# Sheet2.net
KiCad netlist of a schematic drawn in Altium Designer
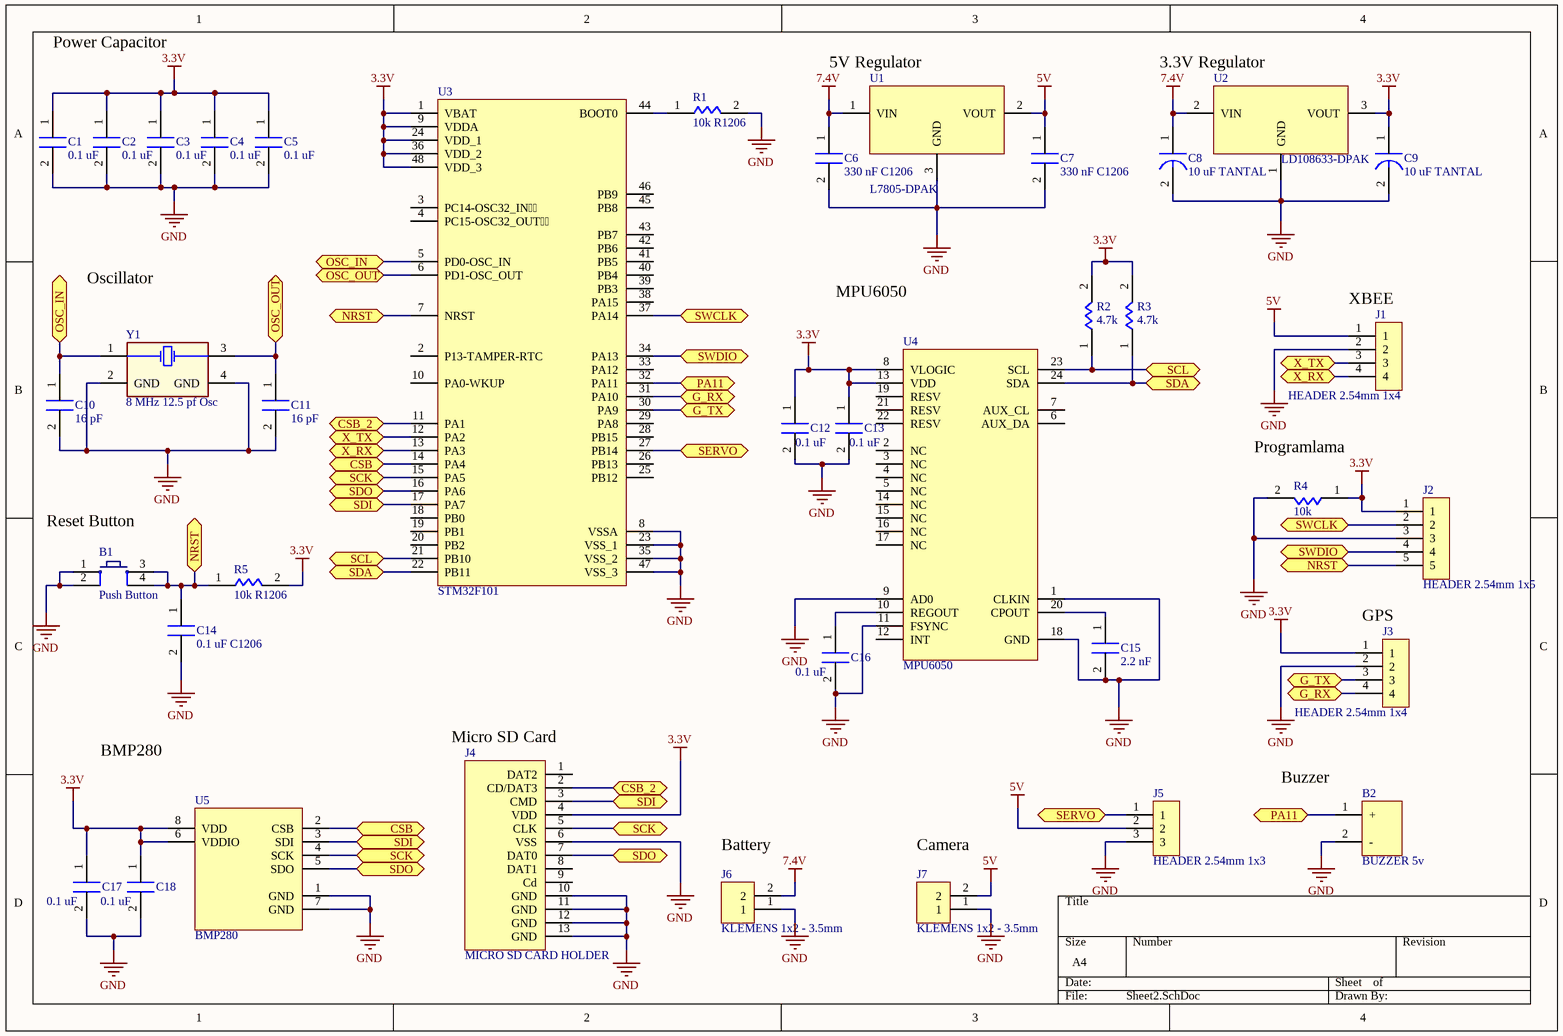
[diagram p0: Sheet2.SchDoc]

(export (version "E")
  (design (tool "Eeschema 10.0.6"))
  (components
    (comp (ref "B1")
      (value "Push Button")
      (footprint "PUSB BUTTON-SMD")
      (description "Smd Push Button")
      (libsource (lib "STM32") (part "Push Button"))
    )
    (comp (ref "B2") (value "BUZZER 5v") (footprint "BUZZER 5v") (libsource (lib "STM32") (part "BUZZER 5v")))
    (comp (ref "C1")
      (value "0.1 uF")
      (footprint "C1206")
      (description "0.1 uF C1206")
      (libsource (lib "STM32") (part "0.1 uF C1206"))
    )
    (comp (ref "C2")
      (value "0.1 uF")
      (footprint "C1206")
      (description "0.1 uF C1206")
      (libsource (lib "STM32") (part "0.1 uF C1206"))
    )
    (comp (ref "C3")
      (value "0.1 uF")
      (footprint "C1206")
      (description "0.1 uF C1206")
      (libsource (lib "STM32") (part "0.1 uF C1206"))
    )
    (comp (ref "C4")
      (value "0.1 uF")
      (footprint "C1206")
      (description "0.1 uF C1206")
      (libsource (lib "STM32") (part "0.1 uF C1206"))
    )
    (comp (ref "C5")
      (value "0.1 uF")
      (footprint "C1206")
      (description "0.1 uF C1206")
      (libsource (lib "STM32") (part "0.1 uF C1206"))
    )
    (comp (ref "C6")
      (value "330 nF C1206")
      (footprint "C1206")
      (libsource (lib "STM32") (part "330 nF C1206"))
    )
    (comp (ref "C7")
      (value "330 nF C1206")
      (footprint "C1206")
      (libsource (lib "STM32") (part "330 nF C1206"))
    )
    (comp (ref "C8")
      (value "10 uF TANTAL")
      (footprint "C1206 - TANTAL")
      (description "10 uF C1206 - TANTAL")
      (libsource (lib "STM32") (part "10 uF TANTAL"))
    )
    (comp (ref "C9")
      (value "10 uF TANTAL")
      (footprint "C1206 - TANTAL")
      (description "10 uF C1206 - TANTAL")
      (libsource (lib "STM32") (part "10 uF TANTAL"))
    )
    (comp (ref "C10") (value "16 pF") (footprint "C1206") (libsource (lib "STM32") (part "16 pF")))
    (comp (ref "C11") (value "16 pF") (footprint "C1206") (libsource (lib "STM32") (part "16 pF")))
    (comp (ref "C12")
      (value "0.1 uF")
      (footprint "C1206")
      (description "0.1 uF C1206")
      (libsource (lib "STM32") (part "0.1 uF C1206"))
    )
    (comp (ref "C13")
      (value "0.1 uF")
      (footprint "C1206")
      (description "0.1 uF C1206")
      (libsource (lib "STM32") (part "0.1 uF C1206"))
    )
    (comp (ref "C14")
      (value "0.1 uF C1206")
      (footprint "C1206")
      (libsource (lib "STM32") (part "0.1 uF C1206"))
    )
    (comp (ref "C15")
      (value "2.2 nF")
      (footprint "C1206")
      (description "2.2 nF C1206")
      (libsource (lib "STM32") (part "2.2 nF"))
    )
    (comp (ref "C16")
      (value "0.1 uF")
      (footprint "C1206")
      (description "0.1 uF C1206")
      (libsource (lib "STM32") (part "0.1 uF C1206"))
    )
    (comp (ref "C17")
      (value "0.1 uF")
      (footprint "C1206")
      (description "0.1 uF C1206")
      (libsource (lib "STM32") (part "0.1 uF C1206"))
    )
    (comp (ref "C18")
      (value "0.1 uF")
      (footprint "C1206")
      (description "0.1 uF C1206")
      (libsource (lib "STM32") (part "0.1 uF C1206"))
    )
    (comp (ref "J1")
      (value "HEADER 2.54mm 1x4")
      (footprint "HEADER 2.54mm 1x4")
      (libsource (lib "STM32") (part "HEADER 2.54mm 1x4"))
    )
    (comp (ref "J2")
      (value "HEADER 2.54mm 1x5")
      (footprint "HEADER 2.54mm 1x5")
      (libsource (lib "STM32") (part "HEADER 2.54mm 1x5"))
    )
    (comp (ref "J3")
      (value "HEADER 2.54mm 1x4")
      (footprint "HEADER 2.54mm 1x4")
      (libsource (lib "STM32") (part "HEADER 2.54mm 1x4"))
    )
    (comp (ref "J4")
      (value "MICRO SD CARD HOLDER")
      (footprint "MICRO SD CARD HOLDER")
      (description "MICRO SD CARD HOLDER KLS1-TF-003 Micro SD Card Connector")
      (libsource (lib "STM32") (part "MICRO SD CARD HOLDER"))
    )
    (comp (ref "J5")
      (value "HEADER 2.54mm 1x3")
      (footprint "HEADER 2.54mm 1x3")
      (libsource (lib "STM32") (part "HEADER 2.54mm 1x3"))
    )
    (comp (ref "J6")
      (value "KLEMENS 1x2 - 3.5mm")
      (footprint "KLEMENS 1x2 - 3.5mm")
      (libsource (lib "STM32") (part "KLEMENS 1x2 - 3.5mm"))
    )
    (comp (ref "J7")
      (value "KLEMENS 1x2 - 3.5mm")
      (footprint "KLEMENS 1x2 - 3.5mm")
      (libsource (lib "STM32") (part "KLEMENS 1x2 - 3.5mm"))
    )
    (comp (ref "R1")
      (value "10k R1206")
      (footprint "R1206 RESISTOR")
      (libsource (lib "STM32") (part "10k R1206"))
    )
    (comp (ref "R2")
      (value "4.7k")
      (footprint "R1206 RESISTOR")
      (description "4.7k R1206")
      (libsource (lib "STM32") (part "4.7k"))
    )
    (comp (ref "R3")
      (value "4.7k")
      (footprint "R1206 RESISTOR")
      (description "4.7k R1206")
      (libsource (lib "STM32") (part "4.7k"))
    )
    (comp (ref "R4")
      (value "10k")
      (footprint "R1206 RESISTOR")
      (description "10k R1206")
      (libsource (lib "STM32") (part "10k"))
    )
    (comp (ref "R5")
      (value "10k R1206")
      (footprint "R1206 RESISTOR")
      (libsource (lib "STM32") (part "10k R1206"))
    )
    (comp (ref "U1")
      (value "L7805-DPAK")
      (footprint "DPAK228P972X240-3N")
      (description "L7805 5V REGULATOR SMD PACKET")
      (libsource (lib "STM32") (part "L7805-DPAK"))
    )
    (comp (ref "U2")
      (value "LD108633-DPAK")
      (footprint "DPAK228P972X240-3N")
      (description "LD108633 3.3V REGULATOR DPAK")
      (libsource (lib "STM32") (part "LD108633-DPAK"))
    )
    (comp (ref "U3")
      (value "STM32F101")
      (footprint "LQPF48_STM")
      (description "STM32F101 48PIN MICROPROCESSOR")
      (libsource (lib "STM32") (part "STM32F101"))
    )
    (comp (ref "U4")
      (value "MPU6050")
      (footprint "QFN50P400X400X95_HS-25N")
      (description "MPU GYRO")
      (libsource (lib "STM32") (part "MPU6050"))
    )
    (comp (ref "U5")
      (value "BMP280")
      (footprint "BMP280")
      (description "BMP280 PRESSURE")
      (libsource (lib "STM32") (part "BMP280"))
    )
    (comp (ref "Y1")
      (value "8 MHz 12.5 pf Osc")
      (footprint "8 MHZ Osc.")
      (libsource (lib "STM32") (part "8 MHz 12.5 pf Osc"))
    )
  )
  (nets
    (net (code "1") (name "/CSB") (class "Default")
      (node (ref "U3") (pin "14") (pinfunction "PA4_14") (pintype "passive"))
      (node (ref "U5") (pin "2") (pinfunction "CSB_2") (pintype "passive"))
    )
    (net (code "2") (name "/CSB_2") (class "Default")
      (node (ref "J4") (pin "2") (pinfunction "CD/DAT3_2") (pintype "passive"))
      (node (ref "U3") (pin "11") (pinfunction "PA1_11") (pintype "passive"))
    )
    (net (code "3") (name "/G_RX") (class "Default")
      (node (ref "J3") (pin "4") (pinfunction "4_4") (pintype "passive"))
      (node (ref "U3") (pin "31") (pinfunction "PA10_31") (pintype "passive"))
    )
    (net (code "4") (name "/G_TX") (class "Default")
      (node (ref "J3") (pin "3") (pinfunction "3_3") (pintype "passive"))
      (node (ref "U3") (pin "30") (pinfunction "PA9_30") (pintype "passive"))
    )
    (net (code "5") (name "/NRST") (class "Default")
      (node (ref "B1") (pin "3") (pinfunction "3_3") (pintype "passive"))
      (node (ref "B1") (pin "4") (pinfunction "4_4") (pintype "passive"))
      (node (ref "C14") (pin "1") (pinfunction "1_1") (pintype "passive"))
      (node (ref "J2") (pin "5") (pinfunction "5_5") (pintype "passive"))
      (node (ref "R5") (pin "1") (pinfunction "1_1") (pintype "passive"))
      (node (ref "U3") (pin "7") (pinfunction "NRST_7") (pintype "passive"))
    )
    (net (code "6") (name "/OSC_IN") (class "Default")
      (node (ref "C10") (pin "1") (pinfunction "1_1") (pintype "passive"))
      (node (ref "U3") (pin "5") (pinfunction "PD0-OSC_IN_5") (pintype "passive"))
      (node (ref "Y1") (pin "1") (pintype "passive"))
    )
    (net (code "7") (name "/OSC_OUT") (class "Default")
      (node (ref "C11") (pin "1") (pinfunction "1_1") (pintype "passive"))
      (node (ref "U3") (pin "6") (pinfunction "PD1-OSC_OUT_6") (pintype "passive"))
      (node (ref "Y1") (pin "3") (pintype "passive"))
    )
    (net (code "8") (name "/PA11") (class "Default")
      (node (ref "B2") (pin "1") (pinfunction "+_1") (pintype "passive"))
      (node (ref "U3") (pin "32") (pinfunction "PA11_32") (pintype "passive"))
    )
    (net (code "9") (name "/SCK") (class "Default")
      (node (ref "J4") (pin "5") (pinfunction "CLK_5") (pintype "passive"))
      (node (ref "U3") (pin "15") (pinfunction "PA5_15") (pintype "passive"))
      (node (ref "U5") (pin "4") (pinfunction "SCK_4") (pintype "passive"))
    )
    (net (code "10") (name "/SCL") (class "Default")
      (node (ref "R2") (pin "1") (pinfunction "1_1") (pintype "passive"))
      (node (ref "U3") (pin "21") (pinfunction "PB10_21") (pintype "passive"))
      (node (ref "U4") (pin "23") (pinfunction "SCL_23") (pintype "passive"))
    )
    (net (code "11") (name "/SDA") (class "Default")
      (node (ref "R3") (pin "1") (pinfunction "1_1") (pintype "passive"))
      (node (ref "U3") (pin "22") (pinfunction "PB11_22") (pintype "passive"))
      (node (ref "U4") (pin "24") (pinfunction "SDA_24") (pintype "passive"))
    )
    (net (code "12") (name "/SDI") (class "Default")
      (node (ref "J4") (pin "3") (pinfunction "CMD_3") (pintype "passive"))
      (node (ref "U3") (pin "17") (pinfunction "PA7_17") (pintype "passive"))
      (node (ref "U5") (pin "3") (pinfunction "SDI_3") (pintype "passive"))
    )
    (net (code "13") (name "/SDO") (class "Default")
      (node (ref "J4") (pin "7") (pinfunction "DAT0_7") (pintype "passive"))
      (node (ref "U3") (pin "16") (pinfunction "PA6_16") (pintype "passive"))
      (node (ref "U5") (pin "5") (pinfunction "SDO_5") (pintype "passive"))
    )
    (net (code "14") (name "/SERVO") (class "Default")
      (node (ref "J5") (pin "1") (pinfunction "1_1") (pintype "passive"))
      (node (ref "U3") (pin "27") (pinfunction "PB14_27") (pintype "passive"))
    )
    (net (code "15") (name "/SWCLK") (class "Default")
      (node (ref "J2") (pin "2") (pinfunction "2_2") (pintype "passive"))
      (node (ref "U3") (pin "37") (pinfunction "PA14_37") (pintype "passive"))
    )
    (net (code "16") (name "/SWDIO") (class "Default")
      (node (ref "J2") (pin "4") (pinfunction "4_4") (pintype "passive"))
      (node (ref "U3") (pin "34") (pinfunction "PA13_34") (pintype "passive"))
    )
    (net (code "17") (name "/X_RX") (class "Default")
      (node (ref "J1") (pin "4") (pinfunction "4_4") (pintype "passive"))
      (node (ref "U3") (pin "13") (pinfunction "PA3_13") (pintype "passive"))
    )
    (net (code "18") (name "/X_TX") (class "Default")
      (node (ref "J1") (pin "3") (pinfunction "3_3") (pintype "passive"))
      (node (ref "U3") (pin "12") (pinfunction "PA2_12") (pintype "passive"))
    )
    (net (code "19") (name "3.3V") (class "Default")
      (node (ref "C1") (pin "1") (pinfunction "1_1") (pintype "passive"))
      (node (ref "C12") (pin "1") (pinfunction "1_1") (pintype "passive"))
      (node (ref "C13") (pin "1") (pinfunction "1_1") (pintype "passive"))
      (node (ref "C17") (pin "1") (pinfunction "1_1") (pintype "passive"))
      (node (ref "C18") (pin "1") (pinfunction "1_1") (pintype "passive"))
      (node (ref "C2") (pin "1") (pinfunction "1_1") (pintype "passive"))
      (node (ref "C3") (pin "1") (pinfunction "1_1") (pintype "passive"))
      (node (ref "C4") (pin "1") (pinfunction "1_1") (pintype "passive"))
      (node (ref "C5") (pin "1") (pinfunction "1_1") (pintype "passive"))
      (node (ref "C9") (pin "1") (pinfunction "1_1") (pintype "passive"))
      (node (ref "J2") (pin "1") (pinfunction "1_1") (pintype "passive"))
      (node (ref "J3") (pin "1") (pinfunction "1_1") (pintype "passive"))
      (node (ref "J4") (pin "4") (pinfunction "VDD_4") (pintype "passive"))
      (node (ref "R2") (pin "2") (pinfunction "2_2") (pintype "passive"))
      (node (ref "R3") (pin "2") (pinfunction "2_2") (pintype "passive"))
      (node (ref "R4") (pin "1") (pinfunction "1_1") (pintype "passive"))
      (node (ref "R5") (pin "2") (pinfunction "2_2") (pintype "passive"))
      (node (ref "U2") (pin "3") (pinfunction "VOUT_3") (pintype "passive"))
      (node (ref "U3") (pin "1") (pinfunction "VBAT_1") (pintype "passive"))
      (node (ref "U3") (pin "24") (pinfunction "VDD_1_24") (pintype "passive"))
      (node (ref "U3") (pin "36") (pinfunction "VDD_2_36") (pintype "passive"))
      (node (ref "U3") (pin "48") (pinfunction "VDD_3_48") (pintype "passive"))
      (node (ref "U3") (pin "9") (pinfunction "VDDA_9") (pintype "passive"))
      (node (ref "U4") (pin "13") (pinfunction "VDD_13") (pintype "passive"))
      (node (ref "U4") (pin "8") (pinfunction "VLOGIC_8") (pintype "passive"))
      (node (ref "U5") (pin "6") (pinfunction "VDDIO_6") (pintype "passive"))
      (node (ref "U5") (pin "8") (pinfunction "VDD_8") (pintype "passive"))
    )
    (net (code "20") (name "5V") (class "Default")
      (node (ref "C7") (pin "1") (pinfunction "1_1") (pintype "passive"))
      (node (ref "J1") (pin "1") (pinfunction "1_1") (pintype "passive"))
      (node (ref "J5") (pin "2") (pinfunction "2_2") (pintype "passive"))
      (node (ref "J7") (pin "2") (pinfunction "2_2") (pintype "passive"))
      (node (ref "U1") (pin "2") (pinfunction "VOUT_2") (pintype "passive"))
    )
    (net (code "21") (name "7.4V") (class "Default")
      (node (ref "C6") (pin "1") (pinfunction "1_1") (pintype "passive"))
      (node (ref "C8") (pin "1") (pinfunction "1_1") (pintype "passive"))
      (node (ref "J6") (pin "2") (pinfunction "2_2") (pintype "passive"))
      (node (ref "U1") (pin "1") (pinfunction "VIN_1") (pintype "passive"))
      (node (ref "U2") (pin "2") (pinfunction "VIN_2") (pintype "passive"))
    )
    (net (code "22") (name "GND") (class "Default")
      (node (ref "B1") (pin "1") (pinfunction "1_1") (pintype "passive"))
      (node (ref "B1") (pin "2") (pinfunction "2_2") (pintype "passive"))
      (node (ref "B2") (pin "2") (pinfunction "-_2") (pintype "passive"))
      (node (ref "C1") (pin "2") (pinfunction "2_2") (pintype "passive"))
      (node (ref "C10") (pin "2") (pinfunction "2_2") (pintype "passive"))
      (node (ref "C11") (pin "2") (pinfunction "2_2") (pintype "passive"))
      (node (ref "C12") (pin "2") (pinfunction "2_2") (pintype "passive"))
      (node (ref "C13") (pin "2") (pinfunction "2_2") (pintype "passive"))
      (node (ref "C14") (pin "2") (pinfunction "2_2") (pintype "passive"))
      (node (ref "C15") (pin "2") (pinfunction "2_2") (pintype "passive"))
      (node (ref "C16") (pin "2") (pinfunction "2_2") (pintype "passive"))
      (node (ref "C17") (pin "2") (pinfunction "2_2") (pintype "passive"))
      (node (ref "C18") (pin "2") (pinfunction "2_2") (pintype "passive"))
      (node (ref "C2") (pin "2") (pinfunction "2_2") (pintype "passive"))
      (node (ref "C3") (pin "2") (pinfunction "2_2") (pintype "passive"))
      (node (ref "C4") (pin "2") (pinfunction "2_2") (pintype "passive"))
      (node (ref "C5") (pin "2") (pinfunction "2_2") (pintype "passive"))
      (node (ref "C6") (pin "2") (pinfunction "2_2") (pintype "passive"))
      (node (ref "C7") (pin "2") (pinfunction "2_2") (pintype "passive"))
      (node (ref "C8") (pin "2") (pinfunction "2_2") (pintype "passive"))
      (node (ref "C9") (pin "2") (pinfunction "2_2") (pintype "passive"))
      (node (ref "J1") (pin "2") (pinfunction "2_2") (pintype "passive"))
      (node (ref "J2") (pin "3") (pinfunction "3_3") (pintype "passive"))
      (node (ref "J3") (pin "2") (pinfunction "2_2") (pintype "passive"))
      (node (ref "J4") (pin "10") (pinfunction "GND_10") (pintype "passive"))
      (node (ref "J4") (pin "11") (pinfunction "GND_11") (pintype "passive"))
      (node (ref "J4") (pin "12") (pinfunction "GND_12") (pintype "passive"))
      (node (ref "J4") (pin "13") (pinfunction "GND_13") (pintype "passive"))
      (node (ref "J4") (pin "6") (pinfunction "VSS_6") (pintype "passive"))
      (node (ref "J5") (pin "3") (pinfunction "3_3") (pintype "passive"))
      (node (ref "J6") (pin "1") (pinfunction "1_1") (pintype "passive"))
      (node (ref "J7") (pin "1") (pinfunction "1_1") (pintype "passive"))
      (node (ref "R1") (pin "2") (pinfunction "2_2") (pintype "passive"))
      (node (ref "R4") (pin "2") (pinfunction "2_2") (pintype "passive"))
      (node (ref "U1") (pin "3") (pinfunction "GND_3") (pintype "passive"))
      (node (ref "U2") (pin "1") (pinfunction "GND_1") (pintype "passive"))
      (node (ref "U3") (pin "23") (pinfunction "VSS_1_23") (pintype "passive"))
      (node (ref "U3") (pin "35") (pinfunction "VSS_2_35") (pintype "passive"))
      (node (ref "U3") (pin "47") (pinfunction "VSS_3_47") (pintype "passive"))
      (node (ref "U3") (pin "8") (pinfunction "VSSA_8") (pintype "passive"))
      (node (ref "U4") (pin "1") (pinfunction "CLKIN_1") (pintype "passive"))
      (node (ref "U4") (pin "11") (pinfunction "FSYNC_11") (pintype "passive"))
      (node (ref "U4") (pin "18") (pinfunction "GND_18") (pintype "passive"))
      (node (ref "U4") (pin "9") (pinfunction "AD0_9") (pintype "passive"))
      (node (ref "U5") (pin "1") (pinfunction "GND_1") (pintype "passive"))
      (node (ref "U5") (pin "7") (pinfunction "GND_7") (pintype "passive"))
      (node (ref "Y1") (pin "2") (pinfunction "GND_2") (pintype "power_in"))
      (node (ref "Y1") (pin "4") (pinfunction "GND_4") (pintype "passive"))
    )
    (net (code "23") (name "Net-(U3-BOOT0)") (class "Default")
      (node (ref "R1") (pin "1") (pinfunction "1_1") (pintype "passive"))
      (node (ref "U3") (pin "44") (pinfunction "BOOT0_44") (pintype "passive"))
    )
    (net (code "24") (name "Net-(U4-CPOUT)") (class "Default")
      (node (ref "C15") (pin "1") (pinfunction "1_1") (pintype "passive"))
      (node (ref "U4") (pin "20") (pinfunction "CPOUT_20") (pintype "passive"))
    )
    (net (code "25") (name "Net-(U4-REGOUT)") (class "Default")
      (node (ref "C16") (pin "1") (pinfunction "1_1") (pintype "passive"))
      (node (ref "U4") (pin "10") (pinfunction "REGOUT_10") (pintype "passive"))
    )
    (net (code "26") (name "unconnected-(J4-Cd-Pad9)") (class "Default")
      (node (ref "J4") (pin "9") (pinfunction "Cd_9") (pintype "passive"))
    )
    (net (code "27") (name "unconnected-(J4-DAT1-Pad8)") (class "Default")
      (node (ref "J4") (pin "8") (pinfunction "DAT1_8") (pintype "passive"))
    )
    (net (code "28") (name "unconnected-(J4-DAT2-Pad1)") (class "Default")
      (node (ref "J4") (pin "1") (pinfunction "DAT2_1") (pintype "passive"))
    )
    (net (code "29") (name "unconnected-(U3-P13-TAMPER-RTC-Pad2)") (class "Default")
      (node (ref "U3") (pin "2") (pinfunction "P13-TAMPER-RTC_2") (pintype "passive"))
    )
    (net (code "30") (name "unconnected-(U3-PA0-WKUP-Pad10)") (class "Default")
      (node (ref "U3") (pin "10") (pinfunction "PA0-WKUP_10") (pintype "passive"))
    )
    (net (code "31") (name "unconnected-(U3-PA8-Pad29)") (class "Default")
      (node (ref "U3") (pin "29") (pinfunction "PA8_29") (pintype "passive"))
    )
    (net (code "32") (name "unconnected-(U3-PA12-Pad33)") (class "Default")
      (node (ref "U3") (pin "33") (pinfunction "PA12_33") (pintype "passive"))
    )
    (net (code "33") (name "unconnected-(U3-PA15-Pad38)") (class "Default")
      (node (ref "U3") (pin "38") (pinfunction "PA15_38") (pintype "passive"))
    )
    (net (code "34") (name "unconnected-(U3-PB0-Pad18)") (class "Default")
      (node (ref "U3") (pin "18") (pinfunction "PB0_18") (pintype "passive"))
    )
    (net (code "35") (name "unconnected-(U3-PB1-Pad19)") (class "Default")
      (node (ref "U3") (pin "19") (pinfunction "PB1_19") (pintype "passive"))
    )
    (net (code "36") (name "unconnected-(U3-PB2-Pad20)") (class "Default")
      (node (ref "U3") (pin "20") (pinfunction "PB2_20") (pintype "passive"))
    )
    (net (code "37") (name "unconnected-(U3-PB3-Pad39)") (class "Default")
      (node (ref "U3") (pin "39") (pinfunction "PB3_39") (pintype "passive"))
    )
    (net (code "38") (name "unconnected-(U3-PB4-Pad40)") (class "Default")
      (node (ref "U3") (pin "40") (pinfunction "PB4_40") (pintype "passive"))
    )
    (net (code "39") (name "unconnected-(U3-PB5-Pad41)") (class "Default")
      (node (ref "U3") (pin "41") (pinfunction "PB5_41") (pintype "passive"))
    )
    (net (code "40") (name "unconnected-(U3-PB6-Pad42)") (class "Default")
      (node (ref "U3") (pin "42") (pinfunction "PB6_42") (pintype "passive"))
    )
    (net (code "41") (name "unconnected-(U3-PB7-Pad43)") (class "Default")
      (node (ref "U3") (pin "43") (pinfunction "PB7_43") (pintype "passive"))
    )
    (net (code "42") (name "unconnected-(U3-PB8-Pad45)") (class "Default")
      (node (ref "U3") (pin "45") (pinfunction "PB8_45") (pintype "passive"))
    )
    (net (code "43") (name "unconnected-(U3-PB9-Pad46)") (class "Default")
      (node (ref "U3") (pin "46") (pinfunction "PB9_46") (pintype "passive"))
    )
    (net (code "44") (name "unconnected-(U3-PB12-Pad25)") (class "Default")
      (node (ref "U3") (pin "25") (pinfunction "PB12_25") (pintype "passive"))
    )
    (net (code "45") (name "unconnected-(U3-PB13-Pad26)") (class "Default")
      (node (ref "U3") (pin "26") (pinfunction "PB13_26") (pintype "passive"))
    )
    (net (code "46") (name "unconnected-(U3-PB15-Pad28)") (class "Default")
      (node (ref "U3") (pin "28") (pinfunction "PB15_28") (pintype "passive"))
    )
    (net (code "47") (name "unconnected-(U3-PC14-OSC32_IN-Pad3)") (class "Default")
      (node (ref "U3") (pin "3") (pinfunction "PC14-OSC32_IN_3") (pintype "passive"))
    )
    (net (code "48") (name "unconnected-(U3-PC15-OSC32_OUT-Pad4)") (class "Default")
      (node (ref "U3") (pin "4") (pinfunction "PC15-OSC32_OUT_4") (pintype "passive"))
    )
    (net (code "49") (name "unconnected-(U4-AUX_CL-Pad7)") (class "Default")
      (node (ref "U4") (pin "7") (pinfunction "AUX_CL_7") (pintype "passive"))
    )
    (net (code "50") (name "unconnected-(U4-AUX_DA-Pad6)") (class "Default")
      (node (ref "U4") (pin "6") (pinfunction "AUX_DA_6") (pintype "passive"))
    )
    (net (code "51") (name "unconnected-(U4-INT-Pad12)") (class "Default")
      (node (ref "U4") (pin "12") (pinfunction "INT_12") (pintype "passive"))
    )
    (net (code "52") (name "unconnected-(U4-NC-Pad2)") (class "Default")
      (node (ref "U4") (pin "2") (pinfunction "NC_2") (pintype "passive"))
    )
    (net (code "53") (name "unconnected-(U4-NC-Pad3)") (class "Default")
      (node (ref "U4") (pin "3") (pinfunction "NC_3") (pintype "passive"))
    )
    (net (code "54") (name "unconnected-(U4-NC-Pad4)") (class "Default")
      (node (ref "U4") (pin "4") (pinfunction "NC_4") (pintype "passive"))
    )
    (net (code "55") (name "unconnected-(U4-NC-Pad5)") (class "Default")
      (node (ref "U4") (pin "5") (pinfunction "NC_5") (pintype "passive"))
    )
    (net (code "56") (name "unconnected-(U4-NC-Pad14)") (class "Default")
      (node (ref "U4") (pin "14") (pinfunction "NC_14") (pintype "passive"))
    )
    (net (code "57") (name "unconnected-(U4-NC-Pad15)") (class "Default")
      (node (ref "U4") (pin "15") (pinfunction "NC_15") (pintype "passive"))
    )
    (net (code "58") (name "unconnected-(U4-NC-Pad16)") (class "Default")
      (node (ref "U4") (pin "16") (pinfunction "NC_16") (pintype "passive"))
    )
    (net (code "59") (name "unconnected-(U4-NC-Pad17)") (class "Default")
      (node (ref "U4") (pin "17") (pinfunction "NC_17") (pintype "passive"))
    )
    (net (code "60") (name "unconnected-(U4-RESV-Pad19)") (class "Default")
      (node (ref "U4") (pin "19") (pinfunction "RESV_19") (pintype "passive"))
    )
    (net (code "61") (name "unconnected-(U4-RESV-Pad21)") (class "Default")
      (node (ref "U4") (pin "21") (pinfunction "RESV_21") (pintype "passive"))
    )
    (net (code "62") (name "unconnected-(U4-RESV-Pad22)") (class "Default")
      (node (ref "U4") (pin "22") (pinfunction "RESV_22") (pintype "passive"))
    )
  )
)
